# LAUNCHXL-F28069_B_1400922_3.net
KiCad netlist of a schematic drawn in Altium Designer
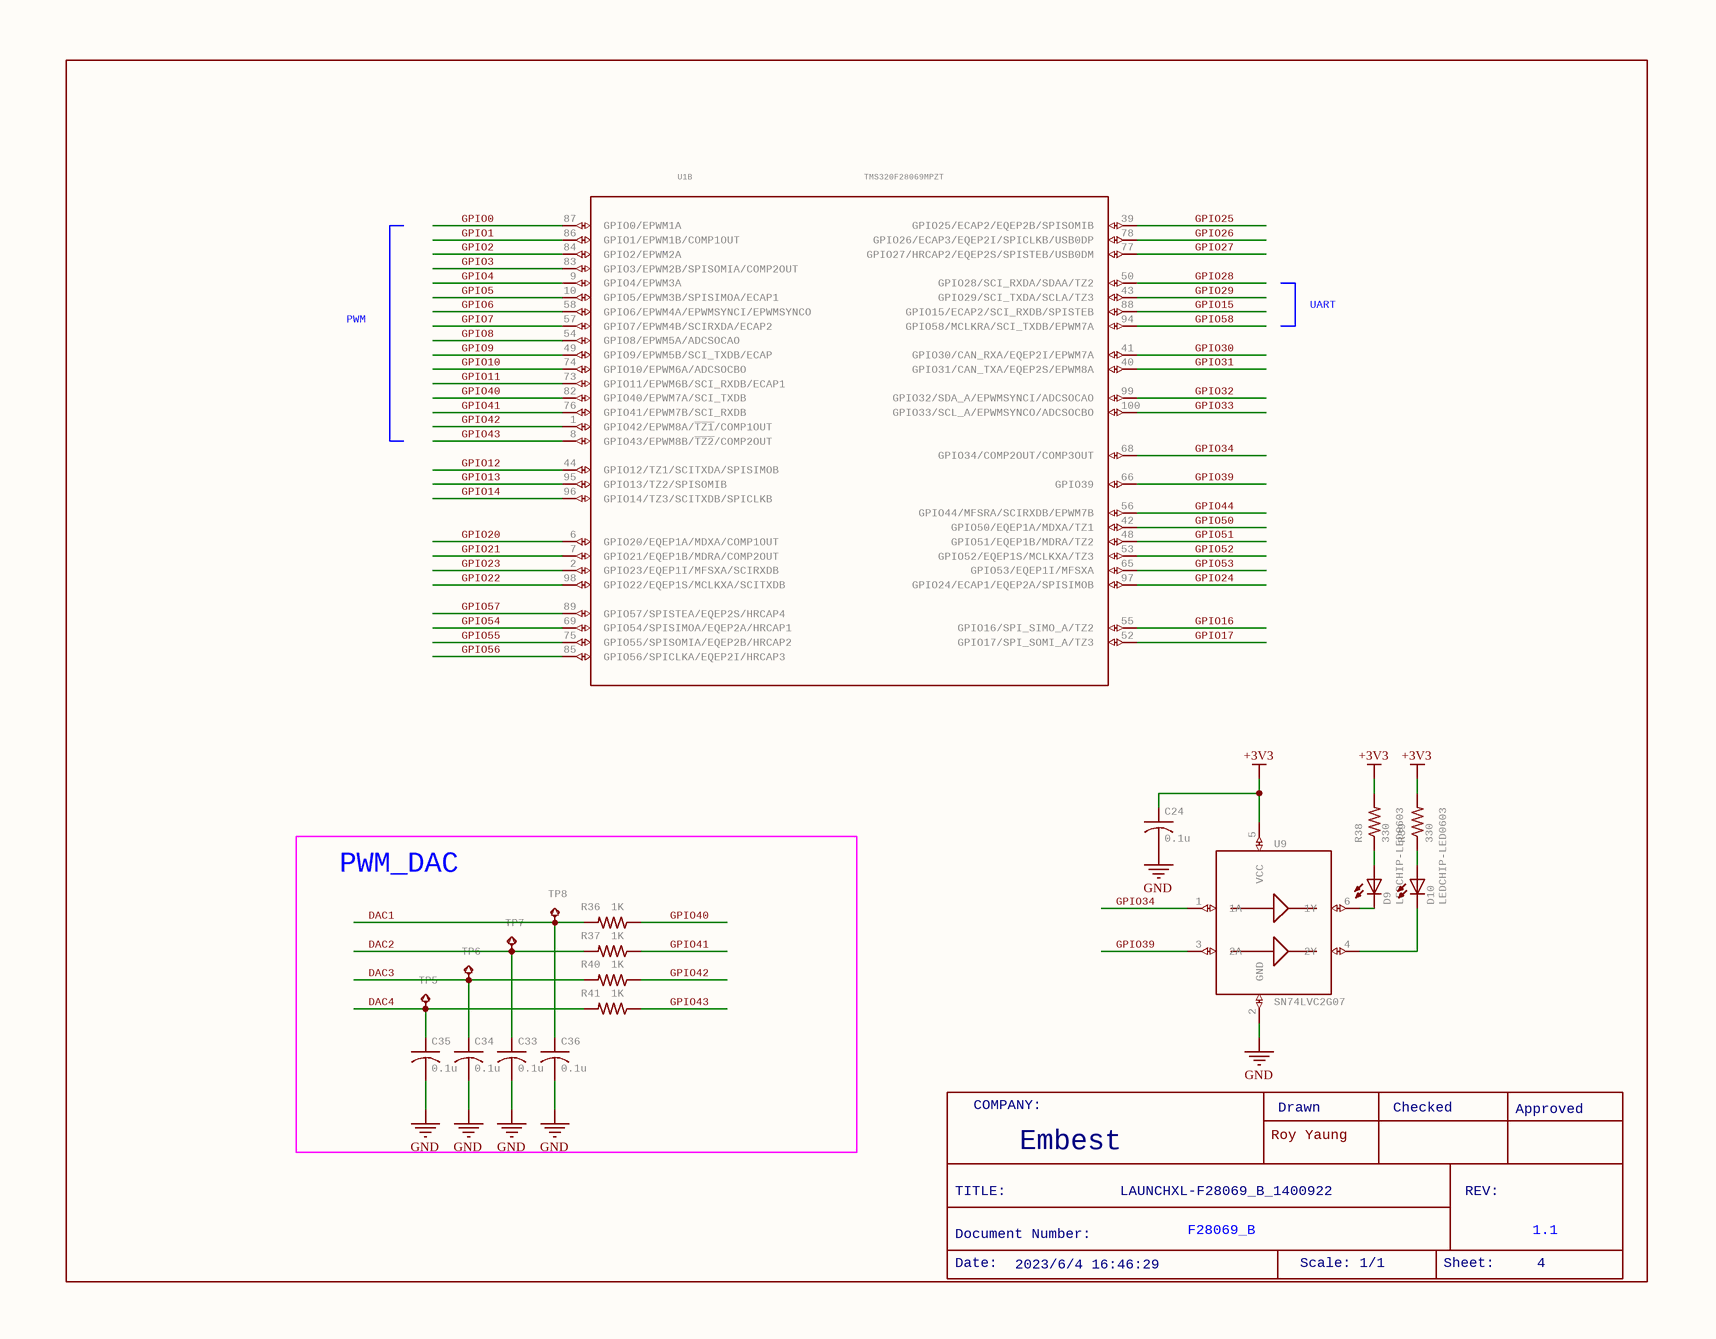
[diagram p0: LAUNCHXL-F28069_B_1400922_3.SchDoc]

(export (version "E")
  (design (tool "Eeschema 10.0.6"))
  (components
    (comp (ref "C24")
      (value "0.1u")
      (footprint "C0402")
      (description "CAPACITOR, American symbol")
      (libsource (lib "rcl") (part "C-USC0402"))
    )
    (comp (ref "C33")
      (value "0.1u")
      (footprint "C0402")
      (description "CAPACITOR, American symbol")
      (libsource (lib "rcl") (part "C-USC0402"))
    )
    (comp (ref "C34")
      (value "0.1u")
      (footprint "C0402")
      (description "CAPACITOR, American symbol")
      (libsource (lib "rcl") (part "C-USC0402"))
    )
    (comp (ref "C35")
      (value "0.1u")
      (footprint "C0402")
      (description "CAPACITOR, American symbol")
      (libsource (lib "rcl") (part "C-USC0402"))
    )
    (comp (ref "C36")
      (value "0.1u")
      (footprint "C0402")
      (description "CAPACITOR, American symbol")
      (libsource (lib "rcl") (part "C-USC0402"))
    )
    (comp (ref "D9")
      (value "LEDCHIP-LED0603")
      (footprint "CHIP-LED0603")
      (libsource (lib "led") (part "LEDCHIP-LED0603"))
    )
    (comp (ref "D10")
      (value "LEDCHIP-LED0603")
      (footprint "CHIP-LED0603")
      (libsource (lib "led") (part "LEDCHIP-LED0603"))
    )
    (comp (ref "R36")
      (value "1K")
      (footprint "R0402")
      (description "RESISTOR, American symbol")
      (libsource (lib "rcl") (part "R-US_R0402"))
    )
    (comp (ref "R37")
      (value "1K")
      (footprint "R0402")
      (description "RESISTOR, American symbol")
      (libsource (lib "rcl") (part "R-US_R0402"))
    )
    (comp (ref "R38")
      (value "330")
      (footprint "R0402")
      (description "RESISTOR, American symbol")
      (libsource (lib "rcl") (part "R-US_R0402"))
    )
    (comp (ref "R39")
      (value "330")
      (footprint "R0402")
      (description "RESISTOR, American symbol")
      (libsource (lib "rcl") (part "R-US_R0402"))
    )
    (comp (ref "R40")
      (value "1K")
      (footprint "R0402")
      (description "RESISTOR, American symbol")
      (libsource (lib "rcl") (part "R-US_R0402"))
    )
    (comp (ref "R41")
      (value "1K")
      (footprint "R0402")
      (description "RESISTOR, American symbol")
      (libsource (lib "rcl") (part "R-US_R0402"))
    )
    (comp (ref "TP5")
      (value "TESTPAD_TPB1,27")
      (footprint "TESTPAD_B1,27")
      (description "Test pad")
      (fields (field (name "LIBRARYNAME") "RF430FRL152H_EVM_a"))
      (libsource (lib "RF430FRL152H_EVM_a") (part "TESTPAD_TPB1,27"))
    )
    (comp (ref "TP6")
      (value "TESTPAD_TPB1,27")
      (footprint "TESTPAD_B1,27")
      (description "Test pad")
      (fields (field (name "LIBRARYNAME") "RF430FRL152H_EVM_a"))
      (libsource (lib "RF430FRL152H_EVM_a") (part "TESTPAD_TPB1,27"))
    )
    (comp (ref "TP7")
      (value "TESTPAD_TPB1,27")
      (footprint "TESTPAD_B1,27")
      (description "Test pad")
      (fields (field (name "LIBRARYNAME") "RF430FRL152H_EVM_a"))
      (libsource (lib "RF430FRL152H_EVM_a") (part "TESTPAD_TPB1,27"))
    )
    (comp (ref "TP8")
      (value "TESTPAD_TPB1,27")
      (footprint "TESTPAD_B1,27")
      (description "Test pad")
      (fields (field (name "LIBRARYNAME") "RF430FRL152H_EVM_a"))
      (libsource (lib "RF430FRL152H_EVM_a") (part "TESTPAD_TPB1,27"))
    )
    (comp (ref "U1")
      (value "TMS320F28069MPZT")
      (footprint "PQFP100")
      (libsource (lib "LAUNCHXL-F28027") (part "TMS320F28069PZSR"))
    )
    (comp (ref "U9")
      (value "SN74LVC2G07")
      (footprint "SOT23-6-DBV")
      (libsource (lib "texas") (part "SN74LVC2G07"))
    )
  )
  (nets
    (net (code "1") (name "+3V3") (class "Default")
      (node (ref "C24") (pin "1") (pinfunction "1_1") (pintype "passive"))
      (node (ref "R38") (pin "2") (pinfunction "2_2") (pintype "passive"))
      (node (ref "R39") (pin "2") (pinfunction "2_2") (pintype "passive"))
      (node (ref "U9") (pin "5") (pinfunction "VCC_5") (pintype "bidirectional"))
    )
    (net (code "2") (name "/DAC1") (class "Default")
      (node (ref "C36") (pin "1") (pinfunction "1_1") (pintype "passive"))
      (node (ref "R36") (pin "2") (pinfunction "2_2") (pintype "passive"))
      (node (ref "TP8") (pin "TP") (pinfunction "TP_TP") (pintype "input"))
    )
    (net (code "3") (name "/DAC2") (class "Default")
      (node (ref "C33") (pin "1") (pinfunction "1_1") (pintype "passive"))
      (node (ref "R37") (pin "2") (pinfunction "2_2") (pintype "passive"))
      (node (ref "TP7") (pin "TP") (pinfunction "TP_TP") (pintype "input"))
    )
    (net (code "4") (name "/DAC3") (class "Default")
      (node (ref "C34") (pin "1") (pinfunction "1_1") (pintype "passive"))
      (node (ref "R40") (pin "2") (pinfunction "2_2") (pintype "passive"))
      (node (ref "TP6") (pin "TP") (pinfunction "TP_TP") (pintype "input"))
    )
    (net (code "5") (name "/DAC4") (class "Default")
      (node (ref "C35") (pin "1") (pinfunction "1_1") (pintype "passive"))
      (node (ref "R41") (pin "2") (pinfunction "2_2") (pintype "passive"))
      (node (ref "TP5") (pin "TP") (pinfunction "TP_TP") (pintype "input"))
    )
    (net (code "6") (name "/GPIO0") (class "Default")
      (node (ref "U1") (pin "87") (pinfunction "GPIO0/EPWM1A_87") (pintype "bidirectional"))
    )
    (net (code "7") (name "/GPIO1") (class "Default")
      (node (ref "U1") (pin "86") (pinfunction "GPIO1/EPWM1B/COMP1OUT_86") (pintype "bidirectional"))
    )
    (net (code "8") (name "/GPIO2") (class "Default")
      (node (ref "U1") (pin "84") (pinfunction "GPIO2/EPWM2A_84") (pintype "bidirectional"))
    )
    (net (code "9") (name "/GPIO3") (class "Default")
      (node (ref "U1") (pin "83") (pinfunction "GPIO3/EPWM2B/SPISOMIA/COMP2OUT_83") (pintype "bidirectional"))
    )
    (net (code "10") (name "/GPIO4") (class "Default")
      (node (ref "U1") (pin "9") (pinfunction "GPIO4/EPWM3A_9") (pintype "bidirectional"))
    )
    (net (code "11") (name "/GPIO5") (class "Default")
      (node (ref "U1") (pin "10") (pinfunction "GPIO5/EPWM3B/SPISIMOA/ECAP1_10") (pintype "bidirectional"))
    )
    (net (code "12") (name "/GPIO6") (class "Default")
      (node (ref "U1") (pin "58") (pinfunction "GPIO6/EPWM4A/EPWMSYNCI/EPWMSYNCO_58") (pintype "bidirectional"))
    )
    (net (code "13") (name "/GPIO7") (class "Default")
      (node (ref "U1") (pin "57") (pinfunction "GPIO7/EPWM4B/SCIRXDA/ECAP2_57") (pintype "bidirectional"))
    )
    (net (code "14") (name "/GPIO8") (class "Default")
      (node (ref "U1") (pin "54") (pinfunction "GPIO8/EPWM5A/ADCSOCAO_54") (pintype "bidirectional"))
    )
    (net (code "15") (name "/GPIO9") (class "Default")
      (node (ref "U1") (pin "49") (pinfunction "GPIO9/EPWM5B/SCI_TXDB/ECAP_49") (pintype "bidirectional"))
    )
    (net (code "16") (name "/GPIO10") (class "Default")
      (node (ref "U1") (pin "74") (pinfunction "GPIO10/EPWM6A/ADCSOCBO_74") (pintype "bidirectional"))
    )
    (net (code "17") (name "/GPIO11") (class "Default")
      (node (ref "U1") (pin "73") (pinfunction "GPIO11/EPWM6B/SCI_RXDB/ECAP1_73") (pintype "bidirectional"))
    )
    (net (code "18") (name "/GPIO12") (class "Default")
      (node (ref "U1") (pin "44") (pinfunction "GPIO12/TZ1/SCITXDA/SPISIMOB_44") (pintype "bidirectional"))
    )
    (net (code "19") (name "/GPIO13") (class "Default")
      (node (ref "U1") (pin "95") (pinfunction "GPIO13/TZ2/SPISOMIB_95") (pintype "bidirectional"))
    )
    (net (code "20") (name "/GPIO14") (class "Default")
      (node (ref "U1") (pin "96") (pinfunction "GPIO14/TZ3/SCITXDB/SPICLKB_96") (pintype "bidirectional"))
    )
    (net (code "21") (name "/GPIO15") (class "Default")
      (node (ref "U1") (pin "88") (pinfunction "GPIO15/ECAP2/SCI_RXDB/SPISTEB_88") (pintype "bidirectional"))
    )
    (net (code "22") (name "/GPIO16") (class "Default")
      (node (ref "U1") (pin "55") (pinfunction "GPIO16/SPI_SIMO_A/TZ2_55") (pintype "bidirectional"))
    )
    (net (code "23") (name "/GPIO17") (class "Default")
      (node (ref "U1") (pin "52") (pinfunction "GPIO17/SPI_SOMI_A/TZ3_52") (pintype "bidirectional"))
    )
    (net (code "24") (name "/GPIO20") (class "Default")
      (node (ref "U1") (pin "6") (pinfunction "GPIO20/EQEP1A/MDXA/COMP1OUT_6") (pintype "bidirectional"))
    )
    (net (code "25") (name "/GPIO21") (class "Default")
      (node (ref "U1") (pin "7") (pinfunction "GPIO21/EQEP1B/MDRA/COMP2OUT_7") (pintype "bidirectional"))
    )
    (net (code "26") (name "/GPIO22") (class "Default")
      (node (ref "U1") (pin "98") (pinfunction "GPIO22/EQEP1S/MCLKXA/SCITXDB_98") (pintype "bidirectional"))
    )
    (net (code "27") (name "/GPIO23") (class "Default")
      (node (ref "U1") (pin "2") (pinfunction "GPIO23/EQEP1I/MFSXA/SCIRXDB_2") (pintype "bidirectional"))
    )
    (net (code "28") (name "/GPIO24") (class "Default")
      (node (ref "U1") (pin "97") (pinfunction "GPIO24/ECAP1/EQEP2A/SPISIMOB_97") (pintype "bidirectional"))
    )
    (net (code "29") (name "/GPIO25") (class "Default")
      (node (ref "U1") (pin "39") (pinfunction "GPIO25/ECAP2/EQEP2B/SPISOMIB_39") (pintype "bidirectional"))
    )
    (net (code "30") (name "/GPIO26") (class "Default")
      (node (ref "U1") (pin "78") (pinfunction "GPIO26/ECAP3/EQEP2I/SPICLKB/USB0DP_78") (pintype "bidirectional"))
    )
    (net (code "31") (name "/GPIO27") (class "Default")
      (node (ref "U1") (pin "77") (pinfunction "GPIO27/HRCAP2/EQEP2S/SPISTEB/USB0DM_77") (pintype "bidirectional"))
    )
    (net (code "32") (name "/GPIO28") (class "Default")
      (node (ref "U1") (pin "50") (pinfunction "GPIO28/SCI_RXDA/SDAA/TZ2_50") (pintype "bidirectional"))
    )
    (net (code "33") (name "/GPIO29") (class "Default")
      (node (ref "U1") (pin "43") (pinfunction "GPIO29/SCI_TXDA/SCLA/TZ3_43") (pintype "bidirectional"))
    )
    (net (code "34") (name "/GPIO30") (class "Default")
      (node (ref "U1") (pin "41") (pinfunction "GPIO30/CAN_RXA/EQEP2I/EPWM7A_41") (pintype "bidirectional"))
    )
    (net (code "35") (name "/GPIO31") (class "Default")
      (node (ref "U1") (pin "40") (pinfunction "GPIO31/CAN_TXA/EQEP2S/EPWM8A_40") (pintype "bidirectional"))
    )
    (net (code "36") (name "/GPIO32") (class "Default")
      (node (ref "U1") (pin "99") (pinfunction "GPIO32/SDA_A/EPWMSYNCI/ADCSOCAO_99") (pintype "bidirectional"))
    )
    (net (code "37") (name "/GPIO33") (class "Default")
      (node (ref "U1") (pin "100") (pinfunction "GPIO33/SCL_A/EPWMSYNCO/ADCSOCBO_100") (pintype "bidirectional"))
    )
    (net (code "38") (name "/GPIO34") (class "Default")
      (node (ref "U1") (pin "68") (pinfunction "GPIO34/COMP2OUT/COMP3OUT_68") (pintype "bidirectional"))
      (node (ref "U9") (pin "1") (pinfunction "1A_1") (pintype "bidirectional"))
    )
    (net (code "39") (name "/GPIO39") (class "Default")
      (node (ref "U1") (pin "66") (pinfunction "GPIO39_66") (pintype "bidirectional"))
      (node (ref "U9") (pin "3") (pinfunction "2A_3") (pintype "bidirectional"))
    )
    (net (code "40") (name "/GPIO40") (class "Default")
      (node (ref "R36") (pin "1") (pinfunction "1_1") (pintype "passive"))
      (node (ref "U1") (pin "82") (pinfunction "GPIO40/EPWM7A/SCI_TXDB_82") (pintype "bidirectional"))
    )
    (net (code "41") (name "/GPIO41") (class "Default")
      (node (ref "R37") (pin "1") (pinfunction "1_1") (pintype "passive"))
      (node (ref "U1") (pin "76") (pinfunction "GPIO41/EPWM7B/SCI_RXDB_76") (pintype "bidirectional"))
    )
    (net (code "42") (name "/GPIO42") (class "Default")
      (node (ref "R40") (pin "1") (pinfunction "1_1") (pintype "passive"))
      (node (ref "U1") (pin "1") (pinfunction "GPIO42/EPWM8A/~{TZ1}/COMP1OUT_1") (pintype "bidirectional"))
    )
    (net (code "43") (name "/GPIO43") (class "Default")
      (node (ref "R41") (pin "1") (pinfunction "1_1") (pintype "passive"))
      (node (ref "U1") (pin "8") (pinfunction "GPIO43/EPWM8B/~{TZ2}/COMP2OUT_8") (pintype "bidirectional"))
    )
    (net (code "44") (name "/GPIO44") (class "Default")
      (node (ref "U1") (pin "56") (pinfunction "GPIO44/MFSRA/SCIRXDB/EPWM7B_56") (pintype "bidirectional"))
    )
    (net (code "45") (name "/GPIO50") (class "Default")
      (node (ref "U1") (pin "42") (pinfunction "GPIO50/EQEP1A/MDXA/TZ1_42") (pintype "bidirectional"))
    )
    (net (code "46") (name "/GPIO51") (class "Default")
      (node (ref "U1") (pin "48") (pinfunction "GPIO51/EQEP1B/MDRA/TZ2_48") (pintype "bidirectional"))
    )
    (net (code "47") (name "/GPIO52") (class "Default")
      (node (ref "U1") (pin "53") (pinfunction "GPIO52/EQEP1S/MCLKXA/TZ3_53") (pintype "bidirectional"))
    )
    (net (code "48") (name "/GPIO53") (class "Default")
      (node (ref "U1") (pin "65") (pinfunction "GPIO53/EQEP1I/MFSXA_65") (pintype "bidirectional"))
    )
    (net (code "49") (name "/GPIO54") (class "Default")
      (node (ref "U1") (pin "69") (pinfunction "GPIO54/SPISIMOA/EQEP2A/HRCAP1_69") (pintype "bidirectional"))
    )
    (net (code "50") (name "/GPIO55") (class "Default")
      (node (ref "U1") (pin "75") (pinfunction "GPIO55/SPISOMIA/EQEP2B/HRCAP2_75") (pintype "bidirectional"))
    )
    (net (code "51") (name "/GPIO56") (class "Default")
      (node (ref "U1") (pin "85") (pinfunction "GPIO56/SPICLKA/EQEP2I/HRCAP3_85") (pintype "bidirectional"))
    )
    (net (code "52") (name "/GPIO57") (class "Default")
      (node (ref "U1") (pin "89") (pinfunction "GPIO57/SPISTEA/EQEP2S/HRCAP4_89") (pintype "bidirectional"))
    )
    (net (code "53") (name "/GPIO58") (class "Default")
      (node (ref "U1") (pin "94") (pinfunction "GPIO58/MCLKRA/SCI_TXDB/EPWM7A_94") (pintype "bidirectional"))
    )
    (net (code "54") (name "GND") (class "Default")
      (node (ref "C24") (pin "2") (pinfunction "2_2") (pintype "passive"))
      (node (ref "C33") (pin "2") (pinfunction "2_2") (pintype "passive"))
      (node (ref "C34") (pin "2") (pinfunction "2_2") (pintype "passive"))
      (node (ref "C35") (pin "2") (pinfunction "2_2") (pintype "passive"))
      (node (ref "C36") (pin "2") (pinfunction "2_2") (pintype "passive"))
      (node (ref "U9") (pin "2") (pinfunction "GND_2") (pintype "bidirectional"))
    )
    (net (code "55") (name "Net-(D9-PadA)") (class "Default")
      (node (ref "D9") (pin "A") (pinfunction "A_A") (pintype "passive"))
      (node (ref "R38") (pin "1") (pinfunction "1_1") (pintype "passive"))
    )
    (net (code "56") (name "Net-(D10-PadA)") (class "Default")
      (node (ref "D10") (pin "A") (pinfunction "A_A") (pintype "passive"))
      (node (ref "R39") (pin "1") (pinfunction "1_1") (pintype "passive"))
    )
    (net (code "57") (name "Net-(U9-1Y)") (class "Default")
      (node (ref "D9") (pin "C") (pinfunction "C_C") (pintype "passive"))
      (node (ref "U9") (pin "6") (pinfunction "1Y_6") (pintype "bidirectional"))
    )
    (net (code "58") (name "Net-(U9-2Y)") (class "Default")
      (node (ref "D10") (pin "C") (pinfunction "C_C") (pintype "passive"))
      (node (ref "U9") (pin "4") (pinfunction "2Y_4") (pintype "bidirectional"))
    )
  )
)
